# pcb_-_vcf_et_etage_sortie.net
KiCad netlist of a schematic drawn in EAGLE
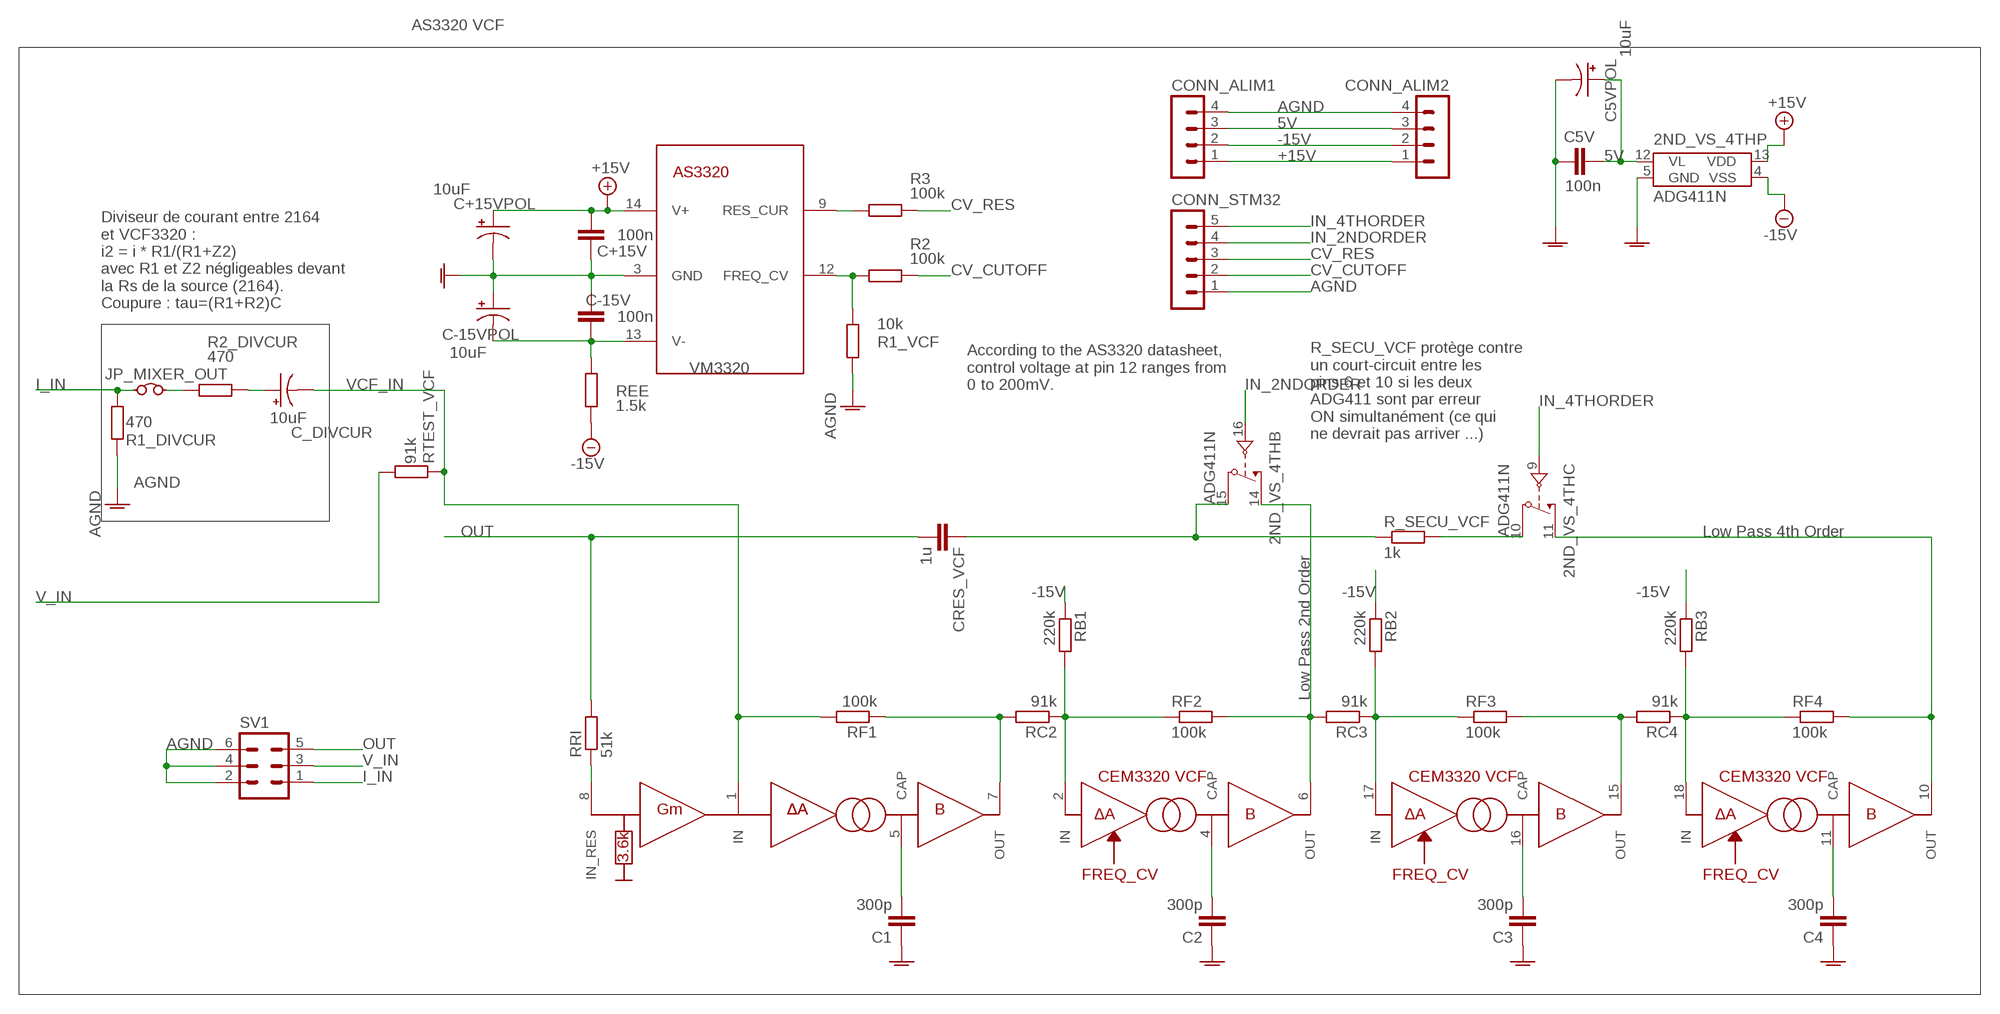
[diagram p0: schematic, sheet 1]

(export (version "E")
  (design (tool "Eeschema 10.0.6"))
  (components
    (comp (ref "2ND_VS_4TH")
      (value "ADG411N")
      (footprint "eagle-import:DIL16")
      (fields (field (name "MF") "ALTERA CORPORATION") (field (name "MPN") "ADG411BN"))
      (libsource (lib "eagle-import") (part "ADG411N"))
    )
    (comp (ref "C+15V")
      (value "100n")
      (footprint "eagle-import:C050-024X044")
      (libsource (lib "eagle-import") (part "C-EU050-024X044"))
    )
    (comp (ref "C+15VPOL")
      (value "10uF")
      (footprint "eagle-import:CPOL-RADIAL-2.5MM-5MM-KIT")
      (libsource (lib "eagle-import") (part "10UF-POLAR-RADIAL-2.5MM-KIT-25V-20%"))
    )
    (comp (ref "C-15V")
      (value "100n")
      (footprint "eagle-import:C050-024X044")
      (libsource (lib "eagle-import") (part "C-EU050-024X044"))
    )
    (comp (ref "C-15VPOL")
      (value "10uF")
      (footprint "eagle-import:CPOL-RADIAL-2.5MM-5MM-KIT")
      (libsource (lib "eagle-import") (part "10UF-POLAR-RADIAL-2.5MM-KIT-25V-20%"))
    )
    (comp (ref "C1")
      (value "300p")
      (footprint "eagle-import:C050-024X044")
      (libsource (lib "eagle-import") (part "C-EU050-024X044"))
    )
    (comp (ref "C2")
      (value "300p")
      (footprint "eagle-import:C050-024X044")
      (libsource (lib "eagle-import") (part "C-EU050-024X044"))
    )
    (comp (ref "C3")
      (value "300p")
      (footprint "eagle-import:C075-032X103")
      (libsource (lib "eagle-import") (part "C-EU075-032X103"))
    )
    (comp (ref "C4")
      (value "300p")
      (footprint "eagle-import:C050-024X044")
      (libsource (lib "eagle-import") (part "C-EU050-024X044"))
    )
    (comp (ref "C5V")
      (value "100n")
      (footprint "eagle-import:C050-024X044")
      (libsource (lib "eagle-import") (part "C-EU050-024X044"))
    )
    (comp (ref "C5VPOL")
      (value "10uF")
      (footprint "eagle-import:CPOL-RADIAL-2.5MM-5MM-KIT")
      (libsource (lib "eagle-import") (part "10UF-POLAR-RADIAL-2.5MM-KIT-25V-20%"))
    )
    (comp (ref "CONN_ALIM1")
      (value "MA04-1")
      (footprint "eagle-import:MA04-1")
      (libsource (lib "eagle-import") (part "MA04-1"))
    )
    (comp (ref "CONN_ALIM2")
      (value "MA04-1")
      (footprint "eagle-import:MA04-1")
      (libsource (lib "eagle-import") (part "MA04-1"))
    )
    (comp (ref "CONN_STM32")
      (value "MA05-1")
      (footprint "eagle-import:MA05-1")
      (libsource (lib "eagle-import") (part "MA05-1"))
    )
    (comp (ref "CRES_VCF")
      (value "1u")
      (footprint "eagle-import:C050-024X044")
      (libsource (lib "eagle-import") (part "C-EU050-024X044"))
    )
    (comp (ref "C_DIVCUR")
      (value "10uF")
      (footprint "eagle-import:CPOL-RADIAL-2.5MM-5MM-KIT")
      (libsource (lib "eagle-import") (part "10UF-POLAR-RADIAL-2.5MM-KIT-25V-20%"))
    )
    (comp (ref "JP_MIXER_OUT")
      (value "JUMPER_WIRE")
      (footprint "eagle-import:JUMPER")
      (libsource (lib "eagle-import") (part "JUMPER_WIRE"))
    )
    (comp (ref "R1_DIVCUR")
      (value "470")
      (footprint "eagle-import:0204_5")
      (libsource (lib "eagle-import") (part "R-EU_0204/5"))
    )
    (comp (ref "R1_VCF")
      (value "10k")
      (footprint "eagle-import:0204_5")
      (libsource (lib "eagle-import") (part "R-EU_0204/5"))
    )
    (comp (ref "R2")
      (value "100k")
      (footprint "eagle-import:0204_5")
      (libsource (lib "eagle-import") (part "R-EU_0204/5"))
    )
    (comp (ref "R2_DIVCUR")
      (value "470")
      (footprint "eagle-import:0204_5")
      (libsource (lib "eagle-import") (part "R-EU_0204/5"))
    )
    (comp (ref "R3")
      (value "100k")
      (footprint "eagle-import:0204_5")
      (libsource (lib "eagle-import") (part "R-EU_0204/5"))
    )
    (comp (ref "RB1")
      (value "220k")
      (footprint "eagle-import:0204_5")
      (libsource (lib "eagle-import") (part "R-EU_0204/5"))
    )
    (comp (ref "RB2")
      (value "220k")
      (footprint "eagle-import:0204_5")
      (libsource (lib "eagle-import") (part "R-EU_0204/5"))
    )
    (comp (ref "RB3")
      (value "220k")
      (footprint "eagle-import:0204_5")
      (libsource (lib "eagle-import") (part "R-EU_0204/5"))
    )
    (comp (ref "RC2")
      (value "91k")
      (footprint "eagle-import:0204_5")
      (libsource (lib "eagle-import") (part "R-EU_0204/5"))
    )
    (comp (ref "RC3")
      (value "91k")
      (footprint "eagle-import:0204_5")
      (libsource (lib "eagle-import") (part "R-EU_0204/5"))
    )
    (comp (ref "RC4")
      (value "91k")
      (footprint "eagle-import:0204_5")
      (libsource (lib "eagle-import") (part "R-EU_0204/5"))
    )
    (comp (ref "REE")
      (value "1.5k")
      (footprint "eagle-import:0204_5")
      (libsource (lib "eagle-import") (part "R-EU_0204/5"))
    )
    (comp (ref "RF1")
      (value "100k")
      (footprint "eagle-import:0204_5")
      (libsource (lib "eagle-import") (part "R-EU_0204/5"))
    )
    (comp (ref "RF2")
      (value "100k")
      (footprint "eagle-import:0204_5")
      (libsource (lib "eagle-import") (part "R-EU_0204/5"))
    )
    (comp (ref "RF3")
      (value "100k")
      (footprint "eagle-import:0204_5")
      (libsource (lib "eagle-import") (part "R-EU_0204/5"))
    )
    (comp (ref "RF4")
      (value "100k")
      (footprint "eagle-import:0204_5")
      (libsource (lib "eagle-import") (part "R-EU_0204/5"))
    )
    (comp (ref "RRI")
      (value "51k")
      (footprint "eagle-import:0204_5")
      (libsource (lib "eagle-import") (part "R-EU_0204/5"))
    )
    (comp (ref "RTEST_VCF")
      (value "91k")
      (footprint "eagle-import:0204_5")
      (libsource (lib "eagle-import") (part "R-EU_0204/5"))
    )
    (comp (ref "R_SECU_VCF")
      (value "1k")
      (footprint "eagle-import:0204_5")
      (libsource (lib "eagle-import") (part "R-EU_0204/5"))
    )
    (comp (ref "SV1")
      (value "MA03-2")
      (footprint "eagle-import:MA03-2")
      (libsource (lib "eagle-import") (part "MA03-2"))
    )
    (comp (ref "VCF")
      (value "AS3320")
      (footprint "eagle-import:DIL18")
      (libsource (lib "eagle-import") (part "AS3320"))
    )
  )
  (nets
    (net (code "1") (name "+15V") (class "Default")
      (node (ref "2ND_VS_4TH") (pin "13") (pinfunction "VDD_13") (pintype "power_in"))
      (node (ref "C+15V") (pin "2") (pinfunction "2_2") (pintype "passive"))
      (node (ref "C+15VPOL") (pin "1") (pinfunction "+_1") (pintype "passive"))
      (node (ref "CONN_ALIM1") (pin "1") (pinfunction "1_1") (pintype "passive"))
      (node (ref "CONN_ALIM2") (pin "1") (pinfunction "1_1") (pintype "passive"))
      (node (ref "VCF") (pin "14") (pinfunction "V+_14") (pintype "bidirectional"))
    )
    (net (code "2") (name "-15V") (class "Default")
      (node (ref "2ND_VS_4TH") (pin "4") (pinfunction "VSS_4") (pintype "power_in"))
      (node (ref "CONN_ALIM1") (pin "2") (pinfunction "2_2") (pintype "passive"))
      (node (ref "CONN_ALIM2") (pin "2") (pinfunction "2_2") (pintype "passive"))
      (node (ref "RB1") (pin "1") (pinfunction "1_1") (pintype "passive"))
      (node (ref "RB2") (pin "1") (pinfunction "1_1") (pintype "passive"))
      (node (ref "RB3") (pin "1") (pinfunction "1_1") (pintype "passive"))
      (node (ref "REE") (pin "1") (pinfunction "1_1") (pintype "passive"))
    )
    (net (code "3") (name "/5V") (class "Default")
      (node (ref "2ND_VS_4TH") (pin "12") (pinfunction "VL_12") (pintype "power_in"))
      (node (ref "C5V") (pin "1") (pinfunction "1_1") (pintype "passive"))
      (node (ref "C5VPOL") (pin "1") (pinfunction "+_1") (pintype "passive"))
      (node (ref "CONN_ALIM1") (pin "3") (pinfunction "3_3") (pintype "passive"))
      (node (ref "CONN_ALIM2") (pin "3") (pinfunction "3_3") (pintype "passive"))
    )
    (net (code "4") (name "/CV_CUTOFF") (class "Default")
      (node (ref "CONN_STM32") (pin "2") (pinfunction "2_2") (pintype "passive"))
      (node (ref "R2") (pin "2") (pinfunction "2_2") (pintype "passive"))
    )
    (net (code "5") (name "/CV_RES") (class "Default")
      (node (ref "CONN_STM32") (pin "3") (pinfunction "3_3") (pintype "passive"))
      (node (ref "R3") (pin "2") (pinfunction "2_2") (pintype "passive"))
    )
    (net (code "6") (name "/IN_2NDORDER") (class "Default")
      (node (ref "2ND_VS_4TH") (pin "16") (pinfunction "IN_16") (pintype "input"))
      (node (ref "CONN_STM32") (pin "4") (pinfunction "4_4") (pintype "passive"))
    )
    (net (code "7") (name "/IN_4THORDER") (class "Default")
      (node (ref "2ND_VS_4TH") (pin "9") (pinfunction "IN_9") (pintype "input"))
      (node (ref "CONN_STM32") (pin "5") (pinfunction "5_5") (pintype "passive"))
    )
    (net (code "8") (name "/I_IN") (class "Default")
      (node (ref "JP_MIXER_OUT") (pin "1") (pinfunction "1_1") (pintype "passive"))
      (node (ref "R1_DIVCUR") (pin "1") (pinfunction "1_1") (pintype "passive"))
      (node (ref "SV1") (pin "1") (pinfunction "1_1") (pintype "passive"))
    )
    (net (code "9") (name "/OUT") (class "Default")
      (node (ref "CRES_VCF") (pin "2") (pinfunction "2_2") (pintype "passive"))
      (node (ref "RRI") (pin "2") (pinfunction "2_2") (pintype "passive"))
      (node (ref "SV1") (pin "5") (pinfunction "5_5") (pintype "passive"))
    )
    (net (code "10") (name "/VCF_IN") (class "Default")
      (node (ref "C_DIVCUR") (pin "2") (pinfunction "-_2") (pintype "passive"))
      (node (ref "RF1") (pin "2") (pinfunction "2_2") (pintype "passive"))
      (node (ref "RTEST_VCF") (pin "2") (pinfunction "2_2") (pintype "passive"))
      (node (ref "VCF") (pin "1") (pinfunction "IN_1") (pintype "bidirectional"))
    )
    (net (code "11") (name "/VM3320") (class "Default")
      (node (ref "C-15V") (pin "1") (pinfunction "1_1") (pintype "passive"))
      (node (ref "C-15VPOL") (pin "2") (pinfunction "-_2") (pintype "passive"))
      (node (ref "REE") (pin "2") (pinfunction "2_2") (pintype "passive"))
      (node (ref "VCF") (pin "13") (pinfunction "V-_13") (pintype "bidirectional"))
    )
    (net (code "12") (name "/V_IN") (class "Default")
      (node (ref "RTEST_VCF") (pin "1") (pinfunction "1_1") (pintype "passive"))
      (node (ref "SV1") (pin "3") (pinfunction "3_3") (pintype "passive"))
    )
    (net (code "13") (name "AGND") (class "Default")
      (node (ref "2ND_VS_4TH") (pin "5") (pinfunction "GND_5") (pintype "power_in"))
      (node (ref "C+15V") (pin "1") (pinfunction "1_1") (pintype "passive"))
      (node (ref "C+15VPOL") (pin "2") (pinfunction "-_2") (pintype "passive"))
      (node (ref "C-15V") (pin "2") (pinfunction "2_2") (pintype "passive"))
      (node (ref "C-15VPOL") (pin "1") (pinfunction "+_1") (pintype "passive"))
      (node (ref "C1") (pin "1") (pinfunction "1_1") (pintype "passive"))
      (node (ref "C2") (pin "1") (pinfunction "1_1") (pintype "passive"))
      (node (ref "C3") (pin "1") (pinfunction "1_1") (pintype "passive"))
      (node (ref "C4") (pin "1") (pinfunction "1_1") (pintype "passive"))
      (node (ref "C5V") (pin "2") (pinfunction "2_2") (pintype "passive"))
      (node (ref "C5VPOL") (pin "2") (pinfunction "-_2") (pintype "passive"))
      (node (ref "CONN_ALIM1") (pin "4") (pinfunction "4_4") (pintype "passive"))
      (node (ref "CONN_ALIM2") (pin "4") (pinfunction "4_4") (pintype "passive"))
      (node (ref "CONN_STM32") (pin "1") (pinfunction "1_1") (pintype "passive"))
      (node (ref "R1_DIVCUR") (pin "2") (pinfunction "2_2") (pintype "passive"))
      (node (ref "R1_VCF") (pin "2") (pinfunction "2_2") (pintype "passive"))
      (node (ref "SV1") (pin "2") (pinfunction "2_2") (pintype "passive"))
      (node (ref "SV1") (pin "4") (pinfunction "4_4") (pintype "passive"))
      (node (ref "SV1") (pin "6") (pinfunction "6_6") (pintype "passive"))
      (node (ref "VCF") (pin "3") (pinfunction "GND_3") (pintype "bidirectional"))
    )
    (net (code "14") (name "Net-(2ND_VS_4THB-D)") (class "Default")
      (node (ref "2ND_VS_4TH") (pin "15") (pinfunction "D_15") (pintype "passive"))
      (node (ref "CRES_VCF") (pin "1") (pinfunction "1_1") (pintype "passive"))
      (node (ref "R_SECU_VCF") (pin "1") (pinfunction "1_1") (pintype "passive"))
    )
    (net (code "15") (name "Net-(2ND_VS_4THB-S)") (class "Default")
      (node (ref "2ND_VS_4TH") (pin "14") (pinfunction "S_14") (pintype "passive"))
      (node (ref "RC3") (pin "2") (pinfunction "2_2") (pintype "passive"))
      (node (ref "RF2") (pin "2") (pinfunction "2_2") (pintype "passive"))
      (node (ref "VCF") (pin "6") (pinfunction "OUT_6") (pintype "bidirectional"))
    )
    (net (code "16") (name "Net-(2ND_VS_4THC-D)") (class "Default")
      (node (ref "2ND_VS_4TH") (pin "10") (pinfunction "D_10") (pintype "passive"))
      (node (ref "R_SECU_VCF") (pin "2") (pinfunction "2_2") (pintype "passive"))
    )
    (net (code "17") (name "Net-(2ND_VS_4THC-S)") (class "Default")
      (node (ref "2ND_VS_4TH") (pin "11") (pinfunction "S_11") (pintype "passive"))
      (node (ref "RF4") (pin "2") (pinfunction "2_2") (pintype "passive"))
      (node (ref "VCF") (pin "10") (pinfunction "OUT_10") (pintype "bidirectional"))
    )
    (net (code "18") (name "Net-(C_DIVCUR-+)") (class "Default")
      (node (ref "C_DIVCUR") (pin "1") (pinfunction "+_1") (pintype "passive"))
      (node (ref "R2_DIVCUR") (pin "1") (pinfunction "1_1") (pintype "passive"))
    )
    (net (code "19") (name "Net-(JP_MIXER_OUT-Pad2)") (class "Default")
      (node (ref "JP_MIXER_OUT") (pin "2") (pinfunction "2_2") (pintype "passive"))
      (node (ref "R2_DIVCUR") (pin "2") (pinfunction "2_2") (pintype "passive"))
    )
    (net (code "20") (name "Net-(VCFA-CAP)") (class "Default")
      (node (ref "C1") (pin "2") (pinfunction "2_2") (pintype "passive"))
      (node (ref "VCF") (pin "5") (pinfunction "CAP_5") (pintype "bidirectional"))
    )
    (net (code "21") (name "Net-(VCFA-IN_RES)") (class "Default")
      (node (ref "RRI") (pin "1") (pinfunction "1_1") (pintype "passive"))
      (node (ref "VCF") (pin "8") (pinfunction "IN_RES_8") (pintype "bidirectional"))
    )
    (net (code "22") (name "Net-(VCFA-OUT)") (class "Default")
      (node (ref "RC2") (pin "2") (pinfunction "2_2") (pintype "passive"))
      (node (ref "RF1") (pin "1") (pinfunction "1_1") (pintype "passive"))
      (node (ref "VCF") (pin "7") (pinfunction "OUT_7") (pintype "bidirectional"))
    )
    (net (code "23") (name "Net-(VCFB-CAP)") (class "Default")
      (node (ref "C2") (pin "2") (pinfunction "2_2") (pintype "passive"))
      (node (ref "VCF") (pin "4") (pinfunction "CAP_4") (pintype "bidirectional"))
    )
    (net (code "24") (name "Net-(VCFB-IN)") (class "Default")
      (node (ref "RB1") (pin "2") (pinfunction "2_2") (pintype "passive"))
      (node (ref "RC2") (pin "1") (pinfunction "1_1") (pintype "passive"))
      (node (ref "RF2") (pin "1") (pinfunction "1_1") (pintype "passive"))
      (node (ref "VCF") (pin "2") (pinfunction "IN_2") (pintype "bidirectional"))
    )
    (net (code "25") (name "Net-(VCFC-CAP)") (class "Default")
      (node (ref "C4") (pin "2") (pinfunction "2_2") (pintype "passive"))
      (node (ref "VCF") (pin "11") (pinfunction "CAP_11") (pintype "bidirectional"))
    )
    (net (code "26") (name "Net-(VCFC-IN)") (class "Default")
      (node (ref "RB3") (pin "2") (pinfunction "2_2") (pintype "passive"))
      (node (ref "RC4") (pin "1") (pinfunction "1_1") (pintype "passive"))
      (node (ref "RF4") (pin "1") (pinfunction "1_1") (pintype "passive"))
      (node (ref "VCF") (pin "18") (pinfunction "IN_18") (pintype "bidirectional"))
    )
    (net (code "27") (name "Net-(VCFD-CAP)") (class "Default")
      (node (ref "C3") (pin "2") (pinfunction "2_2") (pintype "passive"))
      (node (ref "VCF") (pin "16") (pinfunction "CAP_16") (pintype "bidirectional"))
    )
    (net (code "28") (name "Net-(VCFD-IN)") (class "Default")
      (node (ref "RB2") (pin "2") (pinfunction "2_2") (pintype "passive"))
      (node (ref "RC3") (pin "1") (pinfunction "1_1") (pintype "passive"))
      (node (ref "RF3") (pin "1") (pinfunction "1_1") (pintype "passive"))
      (node (ref "VCF") (pin "17") (pinfunction "IN_17") (pintype "bidirectional"))
    )
    (net (code "29") (name "Net-(VCFD-OUT)") (class "Default")
      (node (ref "RC4") (pin "2") (pinfunction "2_2") (pintype "passive"))
      (node (ref "RF3") (pin "2") (pinfunction "2_2") (pintype "passive"))
      (node (ref "VCF") (pin "15") (pinfunction "OUT_15") (pintype "bidirectional"))
    )
    (net (code "30") (name "Net-(VCFE-FREQ_CV)") (class "Default")
      (node (ref "R1_VCF") (pin "1") (pinfunction "1_1") (pintype "passive"))
      (node (ref "R2") (pin "1") (pinfunction "1_1") (pintype "passive"))
      (node (ref "VCF") (pin "12") (pinfunction "FREQ_CV_12") (pintype "bidirectional"))
    )
    (net (code "31") (name "Net-(VCFE-RES_CUR)") (class "Default")
      (node (ref "R3") (pin "1") (pinfunction "1_1") (pintype "passive"))
      (node (ref "VCF") (pin "9") (pinfunction "RES_CUR_9") (pintype "bidirectional"))
    )
  )
)
